# FA58GHZ.net
KiCad netlist of a schematic drawn in EAGLE
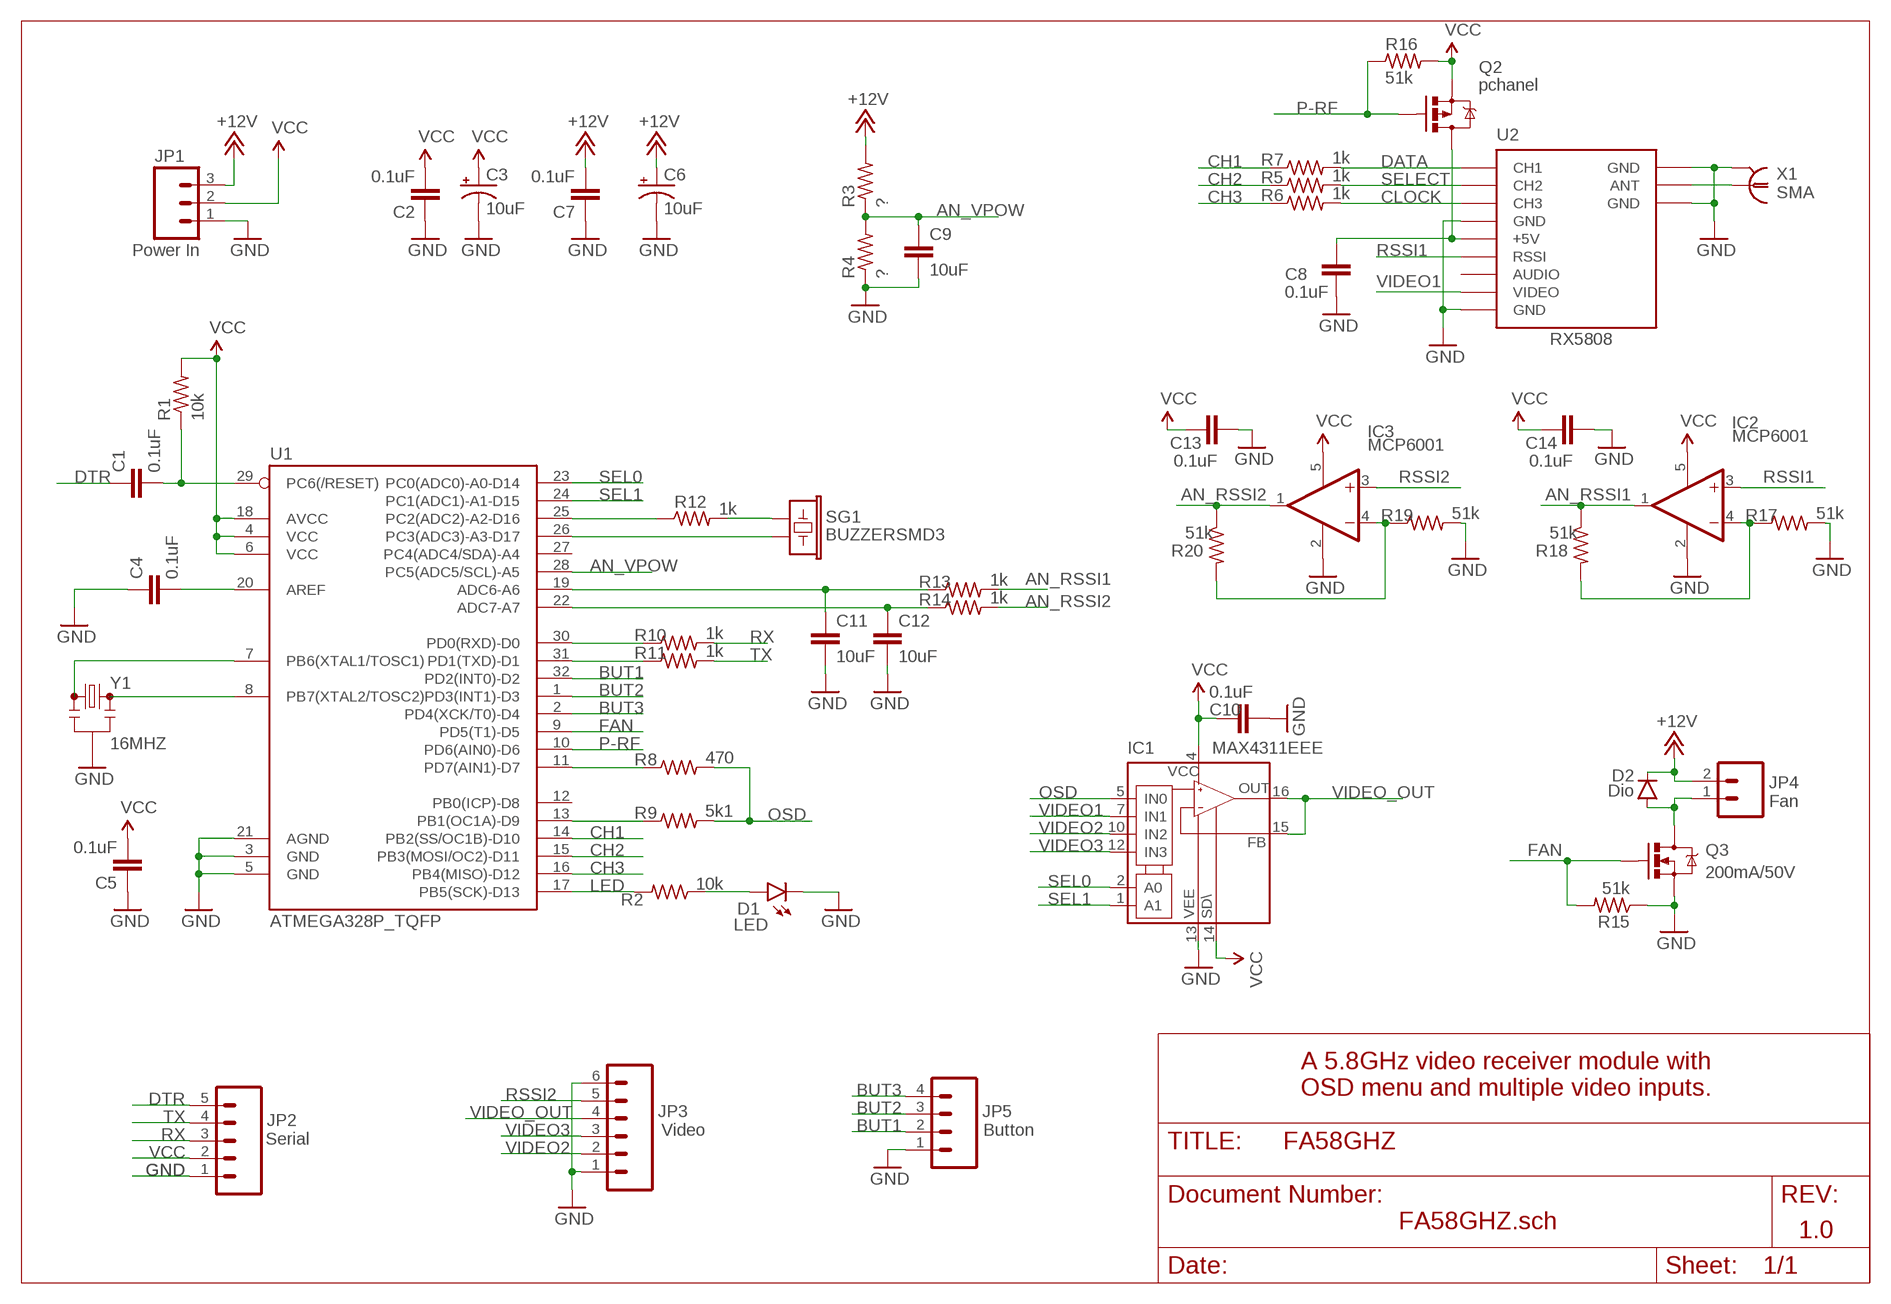
[diagram p0: schematic, sheet 1]

(export (version "E")
  (design (tool "Eeschema 10.0.6"))
  (components
    (comp (ref "C1")
      (value "0.1uF")
      (footprint "eagle-import:C0603")
      (libsource (lib "eagle-import") (part "C-EUC0603"))
    )
    (comp (ref "C2")
      (value "0.1uF")
      (footprint "eagle-import:C0603")
      (libsource (lib "eagle-import") (part "C-EUC0603"))
    )
    (comp (ref "C3")
      (value "10uF")
      (footprint "eagle-import:EIA3216")
      (libsource (lib "eagle-import") (part "10UF-16V-10%(TANT)"))
    )
    (comp (ref "C4")
      (value "0.1uF")
      (footprint "eagle-import:C0603")
      (libsource (lib "eagle-import") (part "C-EUC0603"))
    )
    (comp (ref "C5")
      (value "0.1uF")
      (footprint "eagle-import:C0603")
      (libsource (lib "eagle-import") (part "C-EUC0603"))
    )
    (comp (ref "C6")
      (value "10uF")
      (footprint "eagle-import:EIA3216")
      (libsource (lib "eagle-import") (part "10UF-16V-10%(TANT)"))
    )
    (comp (ref "C7")
      (value "0.1uF")
      (footprint "eagle-import:C0603")
      (libsource (lib "eagle-import") (part "C-EUC0603"))
    )
    (comp (ref "C8")
      (value "0.1uF")
      (footprint "eagle-import:C0603")
      (libsource (lib "eagle-import") (part "C-EUC0603"))
    )
    (comp (ref "C9")
      (value "10uF")
      (footprint "eagle-import:0603-CAP")
      (libsource (lib "eagle-import") (part "CAP0603-CAP"))
    )
    (comp (ref "C10")
      (value "0.1uF")
      (footprint "eagle-import:C0603")
      (libsource (lib "eagle-import") (part "C-EUC0603"))
    )
    (comp (ref "C11")
      (value "10uF")
      (footprint "eagle-import:0603-CAP")
      (libsource (lib "eagle-import") (part "CAP0603-CAP"))
    )
    (comp (ref "C12")
      (value "10uF")
      (footprint "eagle-import:0603-CAP")
      (libsource (lib "eagle-import") (part "CAP0603-CAP"))
    )
    (comp (ref "C13")
      (value "0.1uF")
      (footprint "eagle-import:C0603")
      (libsource (lib "eagle-import") (part "C-EUC0603"))
    )
    (comp (ref "C14")
      (value "0.1uF")
      (footprint "eagle-import:C0603")
      (libsource (lib "eagle-import") (part "C-EUC0603"))
    )
    (comp (ref "D1")
      (value "LED")
      (footprint "eagle-import:LED-0603")
      (libsource (lib "eagle-import") (part "LED0603"))
    )
    (comp (ref "D2")
      (value "Dio")
      (footprint "eagle-import:SOD-323")
      (libsource (lib "eagle-import") (part "DIODEBAS16"))
    )
    (comp (ref "IC1")
      (value "MAX4311EEE")
      (footprint "eagle-import:QSOP16")
      (fields (field (name "MF") "MAXIM") (field (name "MPN") "MAX4311EEE+"))
      (libsource (lib "eagle-import") (part "MAX4311EEE"))
    )
    (comp (ref "IC2")
      (value "MCP6001")
      (footprint "eagle-import:SC70-5")
      (libsource (lib "eagle-import") (part "MCP6001"))
    )
    (comp (ref "IC3")
      (value "MCP6001")
      (footprint "eagle-import:SC70-5")
      (libsource (lib "eagle-import") (part "MCP6001"))
    )
    (comp (ref "JP1")
      (value "Power In")
      (footprint "eagle-import:1X03-1.27MM-OFFSET")
      (libsource (lib "eagle-import") (part "M03"))
    )
    (comp (ref "JP2")
      (value "Serial")
      (footprint "eagle-import:1X05-1.27MM-OFFSET")
      (libsource (lib "eagle-import") (part "M05"))
    )
    (comp (ref "JP3")
      (value "Video")
      (footprint "eagle-import:1X06-1.27MM-OFFSET")
      (libsource (lib "eagle-import") (part "M06"))
    )
    (comp (ref "JP4")
      (value "Fan")
      (footprint "eagle-import:1X02-1.27MM-OFFSET")
      (libsource (lib "eagle-import") (part "M02"))
    )
    (comp (ref "JP5")
      (value "Button")
      (footprint "eagle-import:1X04-1.27MM-OFFSET")
      (libsource (lib "eagle-import") (part "M04"))
    )
    (comp (ref "Q2")
      (value "pchanel")
      (footprint "eagle-import:SOT23-3")
      (libsource (lib "eagle-import") (part "MOSFET-PCHANNEL"))
    )
    (comp (ref "Q3")
      (value "200mA/50V")
      (footprint "eagle-import:SOT23-3")
      (libsource (lib "eagle-import") (part "MOSFET-NCHANNELBSS138"))
    )
    (comp (ref "R1")
      (value "10k")
      (footprint "eagle-import:R0603")
      (libsource (lib "eagle-import") (part "R-US_R0603"))
    )
    (comp (ref "R2")
      (value "10k")
      (footprint "eagle-import:R0603")
      (libsource (lib "eagle-import") (part "R-US_R0603"))
    )
    (comp (ref "R3")
      (value "?")
      (footprint "eagle-import:R0603")
      (libsource (lib "eagle-import") (part "R-US_R0603"))
    )
    (comp (ref "R4")
      (value "?")
      (footprint "eagle-import:R0603")
      (libsource (lib "eagle-import") (part "R-US_R0603"))
    )
    (comp (ref "R5")
      (value "1k")
      (footprint "eagle-import:R0603")
      (libsource (lib "eagle-import") (part "R-US_R0603"))
    )
    (comp (ref "R6")
      (value "1k")
      (footprint "eagle-import:R0603")
      (libsource (lib "eagle-import") (part "R-US_R0603"))
    )
    (comp (ref "R7")
      (value "1k")
      (footprint "eagle-import:R0603")
      (libsource (lib "eagle-import") (part "R-US_R0603"))
    )
    (comp (ref "R8")
      (value "470")
      (footprint "eagle-import:R0603")
      (libsource (lib "eagle-import") (part "R-US_R0603"))
    )
    (comp (ref "R9")
      (value "5k1")
      (footprint "eagle-import:R0603")
      (libsource (lib "eagle-import") (part "R-US_R0603"))
    )
    (comp (ref "R10")
      (value "1k")
      (footprint "eagle-import:R0603")
      (libsource (lib "eagle-import") (part "R-US_R0603"))
    )
    (comp (ref "R11")
      (value "1k")
      (footprint "eagle-import:R0603")
      (libsource (lib "eagle-import") (part "R-US_R0603"))
    )
    (comp (ref "R12")
      (value "1k")
      (footprint "eagle-import:R0603")
      (libsource (lib "eagle-import") (part "R-US_R0603"))
    )
    (comp (ref "R13")
      (value "1k")
      (footprint "eagle-import:R0603")
      (libsource (lib "eagle-import") (part "R-US_R0603"))
    )
    (comp (ref "R14")
      (value "1k")
      (footprint "eagle-import:R0603")
      (libsource (lib "eagle-import") (part "R-US_R0603"))
    )
    (comp (ref "R15")
      (value "51k")
      (footprint "eagle-import:R0603")
      (libsource (lib "eagle-import") (part "R-US_R0603"))
    )
    (comp (ref "R16")
      (value "51k")
      (footprint "eagle-import:R0603")
      (libsource (lib "eagle-import") (part "R-US_R0603"))
    )
    (comp (ref "R17")
      (value "51k")
      (footprint "eagle-import:R0603")
      (libsource (lib "eagle-import") (part "R-US_R0603"))
    )
    (comp (ref "R18")
      (value "51k")
      (footprint "eagle-import:R0603")
      (libsource (lib "eagle-import") (part "R-US_R0603"))
    )
    (comp (ref "R19")
      (value "51k")
      (footprint "eagle-import:R0603")
      (libsource (lib "eagle-import") (part "R-US_R0603"))
    )
    (comp (ref "R20")
      (value "51k")
      (footprint "eagle-import:R0603")
      (libsource (lib "eagle-import") (part "R-US_R0603"))
    )
    (comp (ref "SG1")
      (value "BUZZERSMD3")
      (footprint "eagle-import:BUZZER-12X12X3MM")
      (libsource (lib "eagle-import") (part "BUZZERSMD3"))
    )
    (comp (ref "U1")
      (value "ATMEGA328P_TQFP")
      (footprint "eagle-import:TQFP32-08")
      (libsource (lib "eagle-import") (part "ATMEGA328P_TQFP"))
    )
    (comp (ref "U2")
      (value "RX5808")
      (footprint "eagle-import:RX5808")
      (libsource (lib "eagle-import") (part "RX5808"))
    )
    (comp (ref "X1")
      (value "SMA")
      (footprint "eagle-import:SMA-PCB")
      (libsource (lib "eagle-import") (part "SMA-SMDPCB"))
    )
    (comp (ref "Y1")
      (value "16MHZ")
      (footprint "eagle-import:RESONATOR-SMD")
      (libsource (lib "eagle-import") (part "OSCILLATOR16MHZ"))
    )
  )
  (nets
    (net (code "1") (name "+12V") (class "Default")
      (node (ref "C6") (pin "A") (pinfunction "+_A") (pintype "passive"))
      (node (ref "C7") (pin "2") (pinfunction "2_2") (pintype "passive"))
      (node (ref "D2") (pin "C") (pinfunction "C_C") (pintype "passive"))
      (node (ref "JP1") (pin "3") (pinfunction "3_3") (pintype "passive"))
      (node (ref "JP4") (pin "2") (pinfunction "2_2") (pintype "passive"))
      (node (ref "R3") (pin "2") (pinfunction "2_2") (pintype "passive"))
    )
    (net (code "2") (name "/AN_RSSI1") (class "Default")
      (node (ref "IC2") (pin "1") (pinfunction "OUT_1") (pintype "output"))
      (node (ref "R13") (pin "2") (pinfunction "2_2") (pintype "passive"))
      (node (ref "R18") (pin "1") (pinfunction "1_1") (pintype "passive"))
    )
    (net (code "3") (name "/AN_RSSI2") (class "Default")
      (node (ref "IC3") (pin "1") (pinfunction "OUT_1") (pintype "output"))
      (node (ref "R14") (pin "2") (pinfunction "2_2") (pintype "passive"))
      (node (ref "R20") (pin "1") (pinfunction "1_1") (pintype "passive"))
    )
    (net (code "4") (name "/AN_VPOW") (class "Default")
      (node (ref "C9") (pin "1") (pinfunction "1_1") (pintype "passive"))
      (node (ref "R3") (pin "1") (pinfunction "1_1") (pintype "passive"))
      (node (ref "R4") (pin "2") (pinfunction "2_2") (pintype "passive"))
      (node (ref "U1") (pin "28") (pinfunction "PC5(ADC5/SCL)-A5_28") (pintype "bidirectional"))
    )
    (net (code "5") (name "/BUT1") (class "Default")
      (node (ref "JP5") (pin "2") (pinfunction "2_2") (pintype "passive"))
      (node (ref "U1") (pin "32") (pinfunction "PD2(INT0)-D2_32") (pintype "bidirectional"))
    )
    (net (code "6") (name "/BUT2") (class "Default")
      (node (ref "JP5") (pin "3") (pinfunction "3_3") (pintype "passive"))
      (node (ref "U1") (pin "1") (pinfunction "PD3(INT1)-D3_1") (pintype "bidirectional"))
    )
    (net (code "7") (name "/BUT3") (class "Default")
      (node (ref "JP5") (pin "4") (pinfunction "4_4") (pintype "passive"))
      (node (ref "U1") (pin "2") (pinfunction "PD4(XCK/T0)-D4_2") (pintype "bidirectional"))
    )
    (net (code "8") (name "/CH1") (class "Default")
      (node (ref "R7") (pin "1") (pinfunction "1_1") (pintype "passive"))
      (node (ref "U1") (pin "14") (pinfunction "PB2(SS/OC1B)-D10_14") (pintype "bidirectional"))
    )
    (net (code "9") (name "/CH2") (class "Default")
      (node (ref "R5") (pin "1") (pinfunction "1_1") (pintype "passive"))
      (node (ref "U1") (pin "15") (pinfunction "PB3(MOSI/OC2)-D11_15") (pintype "bidirectional"))
    )
    (net (code "10") (name "/CH3") (class "Default")
      (node (ref "R6") (pin "1") (pinfunction "1_1") (pintype "passive"))
      (node (ref "U1") (pin "16") (pinfunction "PB4(MISO)-D12_16") (pintype "bidirectional"))
    )
    (net (code "11") (name "/CLOCK") (class "Default")
      (node (ref "R6") (pin "2") (pinfunction "2_2") (pintype "passive"))
      (node (ref "U2") (pin "P$7") (pinfunction "CH3_P$7") (pintype "bidirectional"))
    )
    (net (code "12") (name "/DATA") (class "Default")
      (node (ref "R7") (pin "2") (pinfunction "2_2") (pintype "passive"))
      (node (ref "U2") (pin "P$9") (pinfunction "CH1_P$9") (pintype "bidirectional"))
    )
    (net (code "13") (name "/DTR") (class "Default")
      (node (ref "C1") (pin "1") (pinfunction "1_1") (pintype "passive"))
      (node (ref "JP2") (pin "5") (pinfunction "5_5") (pintype "passive"))
    )
    (net (code "14") (name "/FAN") (class "Default")
      (node (ref "Q3") (pin "1") (pinfunction "G_1") (pintype "passive"))
      (node (ref "R15") (pin "2") (pinfunction "2_2") (pintype "passive"))
      (node (ref "U1") (pin "9") (pinfunction "PD5(T1)-D5_9") (pintype "bidirectional"))
    )
    (net (code "15") (name "/LED") (class "Default")
      (node (ref "R2") (pin "2") (pinfunction "2_2") (pintype "passive"))
      (node (ref "U1") (pin "17") (pinfunction "PB5(SCK)-D13_17") (pintype "bidirectional"))
    )
    (net (code "16") (name "/OSD") (class "Default")
      (node (ref "IC1") (pin "5") (pinfunction "IN0_5") (pintype "input"))
      (node (ref "R8") (pin "2") (pinfunction "2_2") (pintype "passive"))
      (node (ref "R9") (pin "2") (pinfunction "2_2") (pintype "passive"))
    )
    (net (code "17") (name "/P-RF") (class "Default")
      (node (ref "Q2") (pin "1") (pinfunction "G_1") (pintype "passive"))
      (node (ref "R16") (pin "1") (pinfunction "1_1") (pintype "passive"))
      (node (ref "U1") (pin "10") (pinfunction "PD6(AIN0)-D6_10") (pintype "bidirectional"))
    )
    (net (code "18") (name "/RSSI1") (class "Default")
      (node (ref "IC2") (pin "3") (pinfunction "+IN_3") (pintype "input"))
      (node (ref "U2") (pin "P$4") (pinfunction "RSSI_P$4") (pintype "bidirectional"))
    )
    (net (code "19") (name "/RSSI2") (class "Default")
      (node (ref "IC3") (pin "3") (pinfunction "+IN_3") (pintype "input"))
      (node (ref "JP3") (pin "5") (pinfunction "5_5") (pintype "passive"))
    )
    (net (code "20") (name "/RX") (class "Default")
      (node (ref "JP2") (pin "3") (pinfunction "3_3") (pintype "passive"))
      (node (ref "R10") (pin "2") (pinfunction "2_2") (pintype "passive"))
    )
    (net (code "21") (name "/SEL0") (class "Default")
      (node (ref "IC1") (pin "2") (pinfunction "A0_2") (pintype "input"))
      (node (ref "U1") (pin "23") (pinfunction "PC0(ADC0)-A0-D14_23") (pintype "bidirectional"))
    )
    (net (code "22") (name "/SEL1") (class "Default")
      (node (ref "IC1") (pin "1") (pinfunction "A1_1") (pintype "input"))
      (node (ref "U1") (pin "24") (pinfunction "PC1(ADC1)-A1-D15_24") (pintype "bidirectional"))
    )
    (net (code "23") (name "/SELECT") (class "Default")
      (node (ref "R5") (pin "2") (pinfunction "2_2") (pintype "passive"))
      (node (ref "U2") (pin "P$8") (pinfunction "CH2_P$8") (pintype "bidirectional"))
    )
    (net (code "24") (name "/TX") (class "Default")
      (node (ref "JP2") (pin "4") (pinfunction "4_4") (pintype "passive"))
      (node (ref "R11") (pin "2") (pinfunction "2_2") (pintype "passive"))
    )
    (net (code "25") (name "/VIDEO1") (class "Default")
      (node (ref "IC1") (pin "7") (pinfunction "IN1_7") (pintype "input"))
      (node (ref "U2") (pin "P$2") (pinfunction "VIDEO_P$2") (pintype "bidirectional"))
    )
    (net (code "26") (name "/VIDEO2") (class "Default")
      (node (ref "IC1") (pin "10") (pinfunction "IN2_10") (pintype "input"))
      (node (ref "JP3") (pin "2") (pinfunction "2_2") (pintype "passive"))
    )
    (net (code "27") (name "/VIDEO3") (class "Default")
      (node (ref "IC1") (pin "12") (pinfunction "IN3_12") (pintype "input"))
      (node (ref "JP3") (pin "3") (pinfunction "3_3") (pintype "passive"))
    )
    (net (code "28") (name "/VIDEO_OUT") (class "Default")
      (node (ref "IC1") (pin "15") (pinfunction "FB_15") (pintype "power_in"))
      (node (ref "IC1") (pin "16") (pinfunction "OUT_16") (pintype "output"))
      (node (ref "JP3") (pin "4") (pinfunction "4_4") (pintype "passive"))
    )
    (net (code "29") (name "GND") (class "Default")
      (node (ref "C10") (pin "1") (pinfunction "1_1") (pintype "passive"))
      (node (ref "C11") (pin "2") (pinfunction "2_2") (pintype "passive"))
      (node (ref "C12") (pin "2") (pinfunction "2_2") (pintype "passive"))
      (node (ref "C13") (pin "2") (pinfunction "2_2") (pintype "passive"))
      (node (ref "C14") (pin "2") (pinfunction "2_2") (pintype "passive"))
      (node (ref "C2") (pin "1") (pinfunction "1_1") (pintype "passive"))
      (node (ref "C3") (pin "C") (pinfunction "-_C") (pintype "passive"))
      (node (ref "C4") (pin "1") (pinfunction "1_1") (pintype "passive"))
      (node (ref "C5") (pin "1") (pinfunction "1_1") (pintype "passive"))
      (node (ref "C6") (pin "C") (pinfunction "-_C") (pintype "passive"))
      (node (ref "C7") (pin "1") (pinfunction "1_1") (pintype "passive"))
      (node (ref "C8") (pin "2") (pinfunction "2_2") (pintype "passive"))
      (node (ref "C9") (pin "2") (pinfunction "2_2") (pintype "passive"))
      (node (ref "D1") (pin "C") (pinfunction "C_C") (pintype "passive"))
      (node (ref "IC1") (pin "13") (pinfunction "V-_13") (pintype "power_in"))
      (node (ref "IC2") (pin "2") (pinfunction "V-_2") (pintype "power_in"))
      (node (ref "IC3") (pin "2") (pinfunction "V-_2") (pintype "power_in"))
      (node (ref "JP1") (pin "1") (pinfunction "1_1") (pintype "passive"))
      (node (ref "JP2") (pin "1") (pinfunction "1_1") (pintype "passive"))
      (node (ref "JP3") (pin "1") (pinfunction "1_1") (pintype "passive"))
      (node (ref "JP3") (pin "6") (pinfunction "6_6") (pintype "passive"))
      (node (ref "JP5") (pin "1") (pinfunction "1_1") (pintype "passive"))
      (node (ref "Q3") (pin "2") (pinfunction "S_2") (pintype "passive"))
      (node (ref "R15") (pin "1") (pinfunction "1_1") (pintype "passive"))
      (node (ref "R17") (pin "2") (pinfunction "2_2") (pintype "passive"))
      (node (ref "R19") (pin "2") (pinfunction "2_2") (pintype "passive"))
      (node (ref "R4") (pin "1") (pinfunction "1_1") (pintype "passive"))
      (node (ref "U1") (pin "21") (pinfunction "AGND_21") (pintype "bidirectional"))
      (node (ref "U1") (pin "3") (pinfunction "GND_3") (pintype "bidirectional"))
      (node (ref "U1") (pin "5") (pinfunction "GND_5") (pintype "bidirectional"))
      (node (ref "U2") (pin "P$1") (pinfunction "GND_P$1") (pintype "bidirectional"))
      (node (ref "U2") (pin "P$10") (pinfunction "GND_P$10") (pintype "bidirectional"))
      (node (ref "U2") (pin "P$12") (pinfunction "GND_P$12") (pintype "bidirectional"))
      (node (ref "U2") (pin "P$6") (pinfunction "GND_P$6") (pintype "bidirectional"))
      (node (ref "X1") (pin "P$1@1") (pinfunction "2_P$1@1") (pintype "passive"))
      (node (ref "X1") (pin "P$1@2") (pinfunction "2_P$1@2") (pintype "passive"))
      (node (ref "Y1") (pin "2") (pinfunction "2_2") (pintype "passive"))
    )
    (net (code "30") (name "Net-(D1-PadA)") (class "Default")
      (node (ref "D1") (pin "A") (pinfunction "A_A") (pintype "passive"))
      (node (ref "R2") (pin "1") (pinfunction "1_1") (pintype "passive"))
    )
    (net (code "31") (name "Net-(IC2--IN)") (class "Default")
      (node (ref "IC2") (pin "4") (pinfunction "-IN_4") (pintype "input"))
      (node (ref "R17") (pin "1") (pinfunction "1_1") (pintype "passive"))
      (node (ref "R18") (pin "2") (pinfunction "2_2") (pintype "passive"))
    )
    (net (code "32") (name "Net-(IC3--IN)") (class "Default")
      (node (ref "IC3") (pin "4") (pinfunction "-IN_4") (pintype "input"))
      (node (ref "R19") (pin "1") (pinfunction "1_1") (pintype "passive"))
      (node (ref "R20") (pin "2") (pinfunction "2_2") (pintype "passive"))
    )
    (net (code "33") (name "Net-(Q2-D)") (class "Default")
      (node (ref "C8") (pin "1") (pinfunction "1_1") (pintype "passive"))
      (node (ref "Q2") (pin "3") (pinfunction "D_3") (pintype "passive"))
      (node (ref "U2") (pin "P$5") (pinfunction "+5V_P$5") (pintype "bidirectional"))
    )
    (net (code "34") (name "Net-(Q3-D)") (class "Default")
      (node (ref "D2") (pin "A") (pinfunction "A_A") (pintype "passive"))
      (node (ref "JP4") (pin "1") (pinfunction "1_1") (pintype "passive"))
      (node (ref "Q3") (pin "3") (pinfunction "D_3") (pintype "passive"))
    )
    (net (code "35") (name "Net-(R12-Pad2)") (class "Default")
      (node (ref "R12") (pin "2") (pinfunction "2_2") (pintype "passive"))
      (node (ref "SG1") (pin "1") (pinfunction "1_1") (pintype "passive"))
    )
    (net (code "36") (name "Net-(U1-ADC6-A6)") (class "Default")
      (node (ref "C11") (pin "1") (pinfunction "1_1") (pintype "passive"))
      (node (ref "R13") (pin "1") (pinfunction "1_1") (pintype "passive"))
      (node (ref "U1") (pin "19") (pinfunction "ADC6-A6_19") (pintype "bidirectional"))
    )
    (net (code "37") (name "Net-(U1-ADC7-A7)") (class "Default")
      (node (ref "C12") (pin "1") (pinfunction "1_1") (pintype "passive"))
      (node (ref "R14") (pin "1") (pinfunction "1_1") (pintype "passive"))
      (node (ref "U1") (pin "22") (pinfunction "ADC7-A7_22") (pintype "bidirectional"))
    )
    (net (code "38") (name "Net-(U1-AREF)") (class "Default")
      (node (ref "C4") (pin "2") (pinfunction "2_2") (pintype "passive"))
      (node (ref "U1") (pin "20") (pinfunction "AREF_20") (pintype "bidirectional"))
    )
    (net (code "39") (name "Net-(U1-PB1(OC1A)-D9)") (class "Default")
      (node (ref "R9") (pin "1") (pinfunction "1_1") (pintype "passive"))
      (node (ref "U1") (pin "13") (pinfunction "PB1(OC1A)-D9_13") (pintype "bidirectional"))
    )
    (net (code "40") (name "Net-(U1-PB6(XTAL1{slash}TOSC1))") (class "Default")
      (node (ref "U1") (pin "7") (pinfunction "PB6(XTAL1/TOSC1)_7") (pintype "bidirectional"))
      (node (ref "Y1") (pin "1") (pinfunction "1_1") (pintype "passive"))
    )
    (net (code "41") (name "Net-(U1-PB7(XTAL2{slash}TOSC2))") (class "Default")
      (node (ref "U1") (pin "8") (pinfunction "PB7(XTAL2/TOSC2)_8") (pintype "bidirectional"))
      (node (ref "Y1") (pin "3") (pinfunction "3_3") (pintype "passive"))
    )
    (net (code "42") (name "Net-(U1-PC2(ADC2)-A2-D16)") (class "Default")
      (node (ref "R12") (pin "1") (pinfunction "1_1") (pintype "passive"))
      (node (ref "U1") (pin "25") (pinfunction "PC2(ADC2)-A2-D16_25") (pintype "bidirectional"))
    )
    (net (code "43") (name "Net-(U1-PC3(ADC3)-A3-D17)") (class "Default")
      (node (ref "SG1") (pin "2") (pinfunction "2_2") (pintype "passive"))
      (node (ref "U1") (pin "26") (pinfunction "PC3(ADC3)-A3-D17_26") (pintype "bidirectional"))
    )
    (net (code "44") (name "Net-(U1-PC6({slash}RESET))") (class "Default")
      (node (ref "C1") (pin "2") (pinfunction "2_2") (pintype "passive"))
      (node (ref "R1") (pin "1") (pinfunction "1_1") (pintype "passive"))
      (node (ref "U1") (pin "29") (pinfunction "PC6(/RESET)_29") (pintype "bidirectional"))
    )
    (net (code "45") (name "Net-(U1-PD0(RXD)-D0)") (class "Default")
      (node (ref "R10") (pin "1") (pinfunction "1_1") (pintype "passive"))
      (node (ref "U1") (pin "30") (pinfunction "PD0(RXD)-D0_30") (pintype "bidirectional"))
    )
    (net (code "46") (name "Net-(U1-PD1(TXD)-D1)") (class "Default")
      (node (ref "R11") (pin "1") (pinfunction "1_1") (pintype "passive"))
      (node (ref "U1") (pin "31") (pinfunction "PD1(TXD)-D1_31") (pintype "bidirectional"))
    )
    (net (code "47") (name "Net-(U1-PD7(AIN1)-D7)") (class "Default")
      (node (ref "R8") (pin "1") (pinfunction "1_1") (pintype "passive"))
      (node (ref "U1") (pin "11") (pinfunction "PD7(AIN1)-D7_11") (pintype "bidirectional"))
    )
    (net (code "48") (name "Net-(U2-ANT)") (class "Default")
      (node (ref "U2") (pin "P$11") (pinfunction "ANT_P$11") (pintype "bidirectional"))
      (node (ref "X1") (pin "P$2") (pinfunction "1_P$2") (pintype "passive"))
    )
    (net (code "49") (name "VCC") (class "Default")
      (node (ref "C10") (pin "2") (pinfunction "2_2") (pintype "passive"))
      (node (ref "C13") (pin "1") (pinfunction "1_1") (pintype "passive"))
      (node (ref "C14") (pin "1") (pinfunction "1_1") (pintype "passive"))
      (node (ref "C2") (pin "2") (pinfunction "2_2") (pintype "passive"))
      (node (ref "C3") (pin "A") (pinfunction "+_A") (pintype "passive"))
      (node (ref "C5") (pin "2") (pinfunction "2_2") (pintype "passive"))
      (node (ref "IC1") (pin "14") (pinfunction "~{SHDN}_14") (pintype "input"))
      (node (ref "IC1") (pin "4") (pinfunction "V+_4") (pintype "power_in"))
      (node (ref "IC2") (pin "5") (pinfunction "V+_5") (pintype "power_in"))
      (node (ref "IC3") (pin "5") (pinfunction "V+_5") (pintype "power_in"))
      (node (ref "JP1") (pin "2") (pinfunction "2_2") (pintype "passive"))
      (node (ref "JP2") (pin "2") (pinfunction "2_2") (pintype "passive"))
      (node (ref "Q2") (pin "2") (pinfunction "S_2") (pintype "passive"))
      (node (ref "R1") (pin "2") (pinfunction "2_2") (pintype "passive"))
      (node (ref "R16") (pin "2") (pinfunction "2_2") (pintype "passive"))
      (node (ref "U1") (pin "18") (pinfunction "AVCC_18") (pintype "bidirectional"))
      (node (ref "U1") (pin "4") (pinfunction "VCC_4") (pintype "bidirectional"))
      (node (ref "U1") (pin "6") (pinfunction "VCC_6") (pintype "bidirectional"))
    )
    (net (code "50") (name "unconnected-(U1-PB0(ICP)-D8-Pad12)") (class "Default")
      (node (ref "U1") (pin "12") (pinfunction "PB0(ICP)-D8_12") (pintype "bidirectional"))
    )
    (net (code "51") (name "unconnected-(U1-PC4(ADC4{slash}SDA)-A4-Pad27)") (class "Default")
      (node (ref "U1") (pin "27") (pinfunction "PC4(ADC4/SDA)-A4_27") (pintype "bidirectional"))
    )
    (net (code "52") (name "unconnected-(U2-AUDIO-PadP$3)") (class "Default")
      (node (ref "U2") (pin "P$3") (pinfunction "AUDIO_P$3") (pintype "bidirectional"))
    )
  )
)
